# micromouse.net
KiCad netlist of a schematic drawn in EAGLE
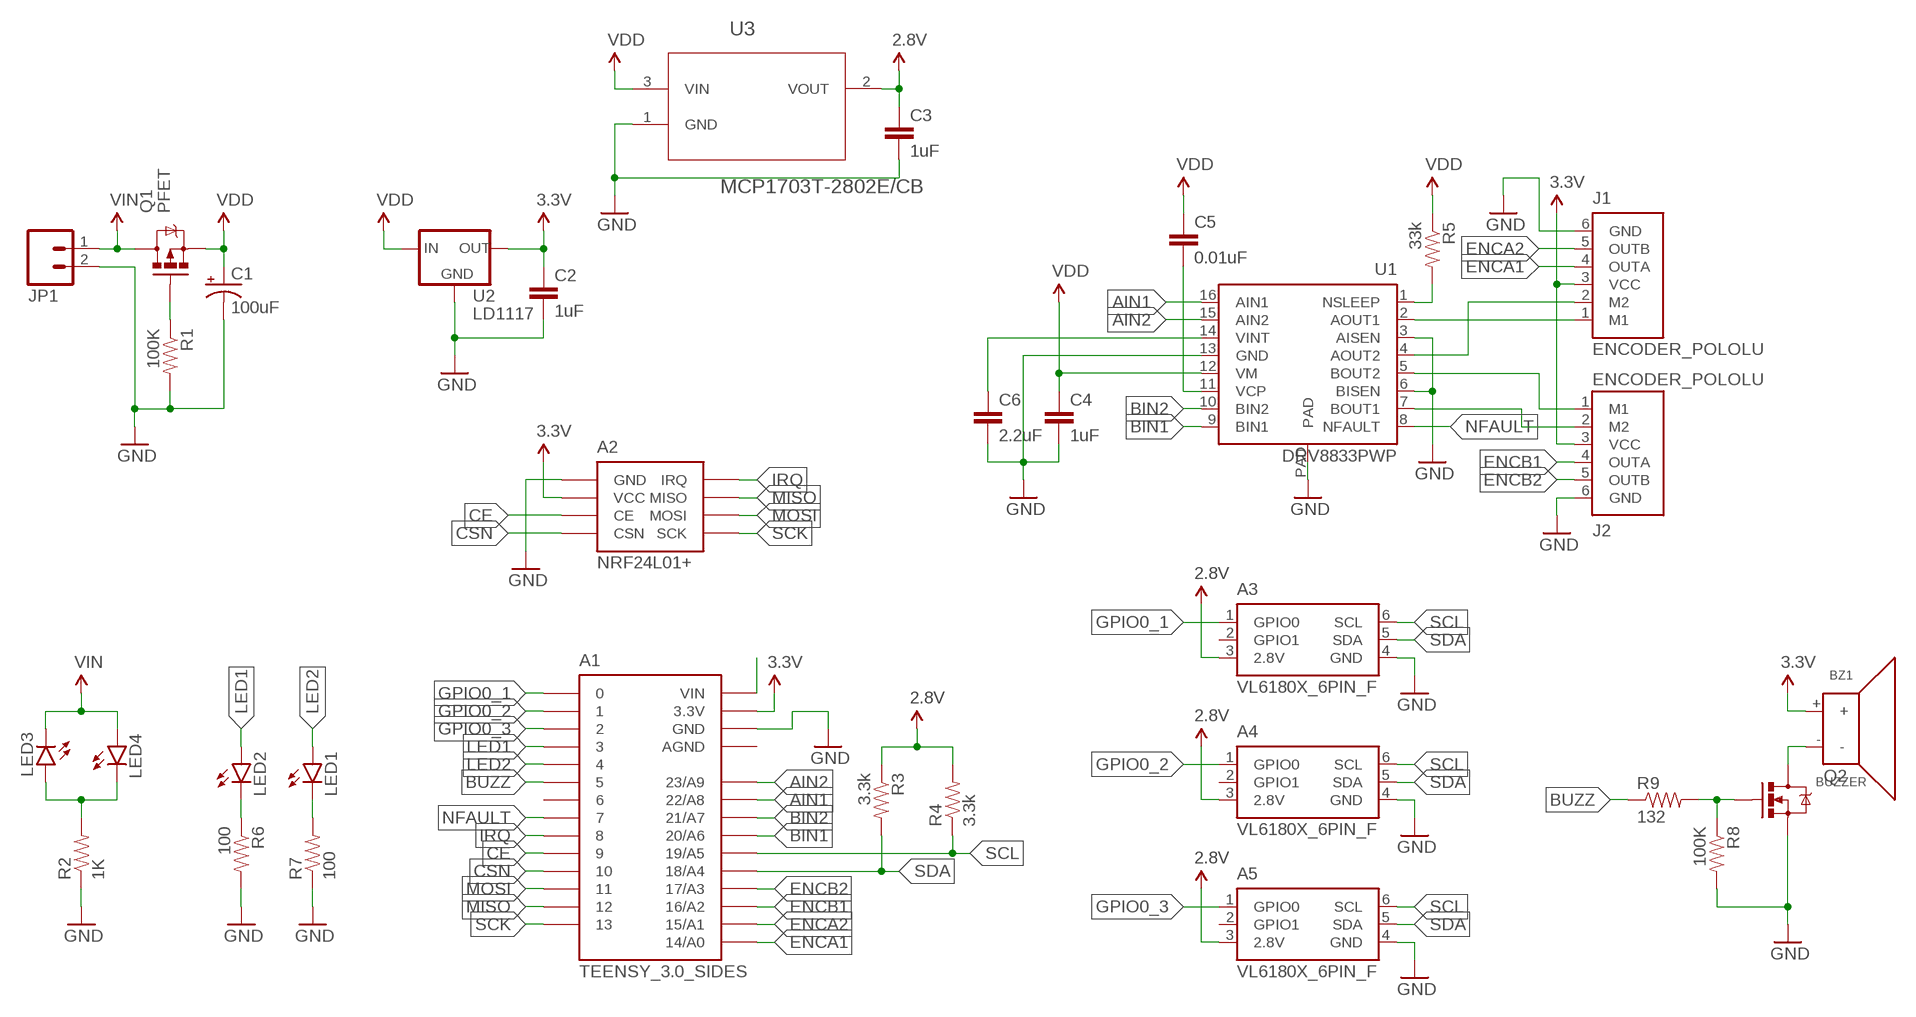
[diagram p0: schematic, sheet 1]

(export (version "E")
  (design (tool "Eeschema 10.0.6"))
  (components
    (comp (ref "A1")
      (value "TEENSY_3.0_SIDES")
      (footprint "eagle-import:TEENSY_3.0_SIDES")
      (libsource (lib "eagle-import") (part "TEENSY_3.0_SIDES"))
    )
    (comp (ref "A2")
      (value "NRF24L01+")
      (footprint "eagle-import:NRF24L01+")
      (libsource (lib "eagle-import") (part "NRF24L01+"))
    )
    (comp (ref "A3")
      (value "VL6180X_6PIN_F")
      (footprint "eagle-import:2X3HEADER")
      (libsource (lib "eagle-import") (part "VL6180X_6PIN_F"))
    )
    (comp (ref "A4")
      (value "VL6180X_6PIN_F")
      (footprint "eagle-import:2X3HEADER")
      (libsource (lib "eagle-import") (part "VL6180X_6PIN_F"))
    )
    (comp (ref "A5")
      (value "VL6180X_6PIN_F")
      (footprint "eagle-import:2X3HEADER")
      (libsource (lib "eagle-import") (part "VL6180X_6PIN_F"))
    )
    (comp (ref "BZ1")
      (value "BUZZER")
      (footprint "eagle-import:BUZZER")
      (libsource (lib "eagle-import") (part "BUZZER"))
    )
    (comp (ref "C1")
      (value "100uF")
      (footprint "eagle-import:CPOL-RADIAL-100UF-25V")
      (libsource (lib "eagle-import") (part "CAP_POLPTH1"))
    )
    (comp (ref "C2")
      (value "1uF")
      (footprint "eagle-import:0603-CAP")
      (libsource (lib "eagle-import") (part "CAP0603-CAP"))
    )
    (comp (ref "C3")
      (value "1uF")
      (footprint "eagle-import:0603-CAP")
      (libsource (lib "eagle-import") (part "CAP0603-CAP"))
    )
    (comp (ref "C4")
      (value "1uF")
      (footprint "eagle-import:0603-CAP")
      (libsource (lib "eagle-import") (part "CAP0603-CAP"))
    )
    (comp (ref "C5")
      (value "0.01uF")
      (footprint "eagle-import:0603-CAP")
      (libsource (lib "eagle-import") (part "CAP0603-CAP"))
    )
    (comp (ref "C6")
      (value "2.2uF")
      (footprint "eagle-import:0603-CAP")
      (libsource (lib "eagle-import") (part "CAP0603-CAP"))
    )
    (comp (ref "J1")
      (value "ENCODER_POLOLU")
      (footprint "eagle-import:1XM06-LOCK")
      (libsource (lib "eagle-import") (part "ENCODER_POLOLU"))
    )
    (comp (ref "J2")
      (value "ENCODER_POLOLU")
      (footprint "eagle-import:1XM06-LOCK")
      (libsource (lib "eagle-import") (part "ENCODER_POLOLU"))
    )
    (comp (ref "JP1")
      (value "M02LOCK_LONGPADS")
      (footprint "eagle-import:1X02_LOCK_LONGPADS")
      (libsource (lib "eagle-import") (part "M02LOCK_LONGPADS"))
    )
    (comp (ref "LED1")
      (value "LED0603")
      (footprint "eagle-import:LED-0603")
      (libsource (lib "eagle-import") (part "LED0603"))
    )
    (comp (ref "LED2")
      (value "LED0603")
      (footprint "eagle-import:LED-0603")
      (libsource (lib "eagle-import") (part "LED0603"))
    )
    (comp (ref "LED3")
      (value "LED0603")
      (footprint "eagle-import:LED-0603")
      (libsource (lib "eagle-import") (part "LED0603"))
    )
    (comp (ref "LED4")
      (value "LED0603")
      (footprint "eagle-import:LED-0603")
      (libsource (lib "eagle-import") (part "LED0603"))
    )
    (comp (ref "Q1")
      (value "PFET")
      (footprint "eagle-import:SOT23-3")
      (libsource (lib "eagle-import") (part "MOSFET-PCHANNEL"))
    )
    (comp (ref "Q2")
      (value "MOSFET-NCHANNELBSS123LT1G")
      (footprint "eagle-import:SOT23-3")
      (libsource (lib "eagle-import") (part "MOSFET-NCHANNELBSS123LT1G"))
    )
    (comp (ref "R1")
      (value "100K")
      (footprint "eagle-import:0603-RES")
      (libsource (lib "eagle-import") (part "RESISTOR0603"))
    )
    (comp (ref "R2")
      (value "1K")
      (footprint "eagle-import:0603-RES")
      (libsource (lib "eagle-import") (part "RESISTOR0603"))
    )
    (comp (ref "R3")
      (value "3.3k")
      (footprint "eagle-import:0603-RES")
      (libsource (lib "eagle-import") (part "RESISTOR0603"))
    )
    (comp (ref "R4")
      (value "3.3k")
      (footprint "eagle-import:0603-RES")
      (libsource (lib "eagle-import") (part "RESISTOR0603"))
    )
    (comp (ref "R5")
      (value "33k")
      (footprint "eagle-import:0603-RES")
      (libsource (lib "eagle-import") (part "RESISTOR0603"))
    )
    (comp (ref "R6")
      (value "100")
      (footprint "eagle-import:0603-RES")
      (libsource (lib "eagle-import") (part "RESISTOR0603"))
    )
    (comp (ref "R7")
      (value "100")
      (footprint "eagle-import:0603-RES")
      (libsource (lib "eagle-import") (part "RESISTOR0603"))
    )
    (comp (ref "R8")
      (value "100K")
      (footprint "eagle-import:0603-RES")
      (libsource (lib "eagle-import") (part "RESISTOR0603"))
    )
    (comp (ref "R9")
      (value "132")
      (footprint "eagle-import:0603-RES")
      (libsource (lib "eagle-import") (part "RESISTOR0603"))
    )
    (comp (ref "U1")
      (value "DRV8833PWP")
      (footprint "eagle-import:HTSSOP-16")
      (libsource (lib "eagle-import") (part "DRV8833PWP"))
    )
    (comp (ref "U2")
      (value "LD1117")
      (footprint "eagle-import:SOT-223")
      (libsource (lib "eagle-import") (part "LD1117"))
    )
    (comp (ref "U3")
      (value "MCP1703T-2802E/CB")
      (footprint "eagle-import:SOT95P300X145-3N")
      (fields (field (name "MPN") "MCP1703T-3002E/CB"))
      (libsource (lib "eagle-import") (part "MCP1703T-3002E/CB"))
    )
  )
  (nets
    (net (code "1") (name "/AGND") (class "Default")
      (node (ref "A1") (pin "AGND") (pinfunction "AGND_AGND") (pintype "power_in"))
    )
    (net (code "2") (name "2.8V") (class "Default")
      (node (ref "A3") (pin "3") (pinfunction "2.8V_3") (pintype "bidirectional"))
      (node (ref "A4") (pin "3") (pinfunction "2.8V_3") (pintype "bidirectional"))
      (node (ref "A5") (pin "3") (pinfunction "2.8V_3") (pintype "bidirectional"))
      (node (ref "C3") (pin "1") (pinfunction "1_1") (pintype "passive"))
      (node (ref "R3") (pin "1") (pinfunction "1_1") (pintype "passive"))
      (node (ref "R4") (pin "2") (pinfunction "2_2") (pintype "passive"))
      (node (ref "U3") (pin "2") (pinfunction "VOUT_2") (pintype "output"))
    )
    (net (code "3") (name "3.3V") (class "Default")
      (node (ref "A1") (pin "3.3V") (pinfunction "3.3V_3.3V") (pintype "power_in"))
      (node (ref "A2") (pin "2") (pinfunction "VCC_2") (pintype "bidirectional"))
      (node (ref "BZ1") (pin "+") (pinfunction "+_+") (pintype "bidirectional"))
      (node (ref "C2") (pin "1") (pinfunction "1_1") (pintype "passive"))
      (node (ref "J1") (pin "3") (pinfunction "VCC_3") (pintype "bidirectional"))
      (node (ref "J2") (pin "3") (pinfunction "VCC_3") (pintype "bidirectional"))
      (node (ref "U2") (pin "2") (pinfunction "OUT_2") (pintype "passive"))
      (node (ref "U2") (pin "4") (pinfunction "OUT_4") (pintype "passive"))
    )
    (net (code "4") (name "AIN1") (class "Default")
      (node (ref "A1") (pin "22/A8") (pinfunction "22/A8_22/A8") (pintype "bidirectional"))
      (node (ref "U1") (pin "16") (pinfunction "AIN1_16") (pintype "bidirectional"))
    )
    (net (code "5") (name "AIN2") (class "Default")
      (node (ref "A1") (pin "23/A9") (pinfunction "23/A9_23/A9") (pintype "bidirectional"))
      (node (ref "U1") (pin "15") (pinfunction "AIN2_15") (pintype "bidirectional"))
    )
    (net (code "6") (name "BIN1") (class "Default")
      (node (ref "A1") (pin "20/A6") (pinfunction "20/A6_20/A6") (pintype "bidirectional"))
      (node (ref "U1") (pin "9") (pinfunction "BIN1_9") (pintype "bidirectional"))
    )
    (net (code "7") (name "BIN2") (class "Default")
      (node (ref "A1") (pin "21/A7") (pinfunction "21/A7_21/A7") (pintype "bidirectional"))
      (node (ref "U1") (pin "10") (pinfunction "BIN2_10") (pintype "bidirectional"))
    )
    (net (code "8") (name "BUZZ") (class "Default")
      (node (ref "A1") (pin "5") (pinfunction "5_5") (pintype "bidirectional"))
      (node (ref "R9") (pin "1") (pinfunction "1_1") (pintype "passive"))
    )
    (net (code "9") (name "CE") (class "Default")
      (node (ref "A1") (pin "9") (pinfunction "9_9") (pintype "bidirectional"))
      (node (ref "A2") (pin "3") (pinfunction "CE_3") (pintype "bidirectional"))
    )
    (net (code "10") (name "CSN") (class "Default")
      (node (ref "A1") (pin "10") (pinfunction "10_10") (pintype "bidirectional"))
      (node (ref "A2") (pin "4") (pinfunction "CSN_4") (pintype "bidirectional"))
    )
    (net (code "11") (name "ENCA1") (class "Default")
      (node (ref "A1") (pin "14/A0") (pinfunction "14/A0_14/A0") (pintype "bidirectional"))
      (node (ref "J1") (pin "4") (pinfunction "OUTA_4") (pintype "bidirectional"))
    )
    (net (code "12") (name "ENCA2") (class "Default")
      (node (ref "A1") (pin "15/A1") (pinfunction "15/A1_15/A1") (pintype "bidirectional"))
      (node (ref "J1") (pin "5") (pinfunction "OUTB_5") (pintype "bidirectional"))
    )
    (net (code "13") (name "ENCB1") (class "Default")
      (node (ref "A1") (pin "16/A2") (pinfunction "16/A2_16/A2") (pintype "bidirectional"))
      (node (ref "J2") (pin "4") (pinfunction "OUTA_4") (pintype "bidirectional"))
    )
    (net (code "14") (name "ENCB2") (class "Default")
      (node (ref "A1") (pin "17/A3") (pinfunction "17/A3_17/A3") (pintype "bidirectional"))
      (node (ref "J2") (pin "5") (pinfunction "OUTB_5") (pintype "bidirectional"))
    )
    (net (code "15") (name "GND") (class "Default")
      (node (ref "A1") (pin "GND") (pinfunction "GND_GND") (pintype "power_in"))
      (node (ref "A2") (pin "1") (pinfunction "GND_1") (pintype "bidirectional"))
      (node (ref "A3") (pin "4") (pinfunction "GND_4") (pintype "bidirectional"))
      (node (ref "A4") (pin "4") (pinfunction "GND_4") (pintype "bidirectional"))
      (node (ref "A5") (pin "4") (pinfunction "GND_4") (pintype "bidirectional"))
      (node (ref "C1") (pin "2") (pinfunction "-_2") (pintype "passive"))
      (node (ref "C2") (pin "2") (pinfunction "2_2") (pintype "passive"))
      (node (ref "C3") (pin "2") (pinfunction "2_2") (pintype "passive"))
      (node (ref "C4") (pin "2") (pinfunction "2_2") (pintype "passive"))
      (node (ref "C6") (pin "2") (pinfunction "2_2") (pintype "passive"))
      (node (ref "J1") (pin "6") (pinfunction "GND_6") (pintype "bidirectional"))
      (node (ref "J2") (pin "6") (pinfunction "GND_6") (pintype "bidirectional"))
      (node (ref "JP1") (pin "2") (pinfunction "2_2") (pintype "passive"))
      (node (ref "Q2") (pin "2") (pinfunction "S_2") (pintype "passive"))
      (node (ref "R1") (pin "2") (pinfunction "2_2") (pintype "passive"))
      (node (ref "R2") (pin "1") (pinfunction "1_1") (pintype "passive"))
      (node (ref "R6") (pin "2") (pinfunction "2_2") (pintype "passive"))
      (node (ref "R7") (pin "1") (pinfunction "1_1") (pintype "passive"))
      (node (ref "R8") (pin "2") (pinfunction "2_2") (pintype "passive"))
      (node (ref "U1") (pin "13") (pinfunction "GND_13") (pintype "bidirectional"))
      (node (ref "U1") (pin "3") (pinfunction "AISEN_3") (pintype "bidirectional"))
      (node (ref "U1") (pin "6") (pinfunction "BISEN_6") (pintype "bidirectional"))
      (node (ref "U1") (pin "PAD") (pinfunction "PAD_PAD") (pintype "bidirectional"))
      (node (ref "U2") (pin "1") (pinfunction "GND_1") (pintype "input"))
      (node (ref "U3") (pin "1") (pinfunction "GND_1") (pintype "passive"))
    )
    (net (code "16") (name "GPIO0_1") (class "Default")
      (node (ref "A1") (pin "0") (pinfunction "0_0") (pintype "bidirectional"))
      (node (ref "A3") (pin "1") (pinfunction "GPIO0_1") (pintype "bidirectional"))
    )
    (net (code "17") (name "GPIO0_2") (class "Default")
      (node (ref "A1") (pin "1") (pinfunction "1_1") (pintype "bidirectional"))
      (node (ref "A4") (pin "1") (pinfunction "GPIO0_1") (pintype "bidirectional"))
    )
    (net (code "18") (name "GPIO0_3") (class "Default")
      (node (ref "A1") (pin "2") (pinfunction "2_2") (pintype "bidirectional"))
      (node (ref "A5") (pin "1") (pinfunction "GPIO0_1") (pintype "bidirectional"))
    )
    (net (code "19") (name "IRQ") (class "Default")
      (node (ref "A1") (pin "8") (pinfunction "8_8") (pintype "bidirectional"))
      (node (ref "A2") (pin "8") (pinfunction "IRQ_8") (pintype "bidirectional"))
    )
    (net (code "20") (name "LED1") (class "Default")
      (node (ref "A1") (pin "3") (pinfunction "3_3") (pintype "bidirectional"))
      (node (ref "LED2") (pin "A") (pinfunction "A_A") (pintype "passive"))
    )
    (net (code "21") (name "LED2") (class "Default")
      (node (ref "A1") (pin "4") (pinfunction "4_4") (pintype "bidirectional"))
      (node (ref "LED1") (pin "A") (pinfunction "A_A") (pintype "passive"))
    )
    (net (code "22") (name "MISO") (class "Default")
      (node (ref "A1") (pin "12") (pinfunction "12_12") (pintype "bidirectional"))
      (node (ref "A2") (pin "7") (pinfunction "MISO_7") (pintype "bidirectional"))
    )
    (net (code "23") (name "MOSI") (class "Default")
      (node (ref "A1") (pin "11") (pinfunction "11_11") (pintype "bidirectional"))
      (node (ref "A2") (pin "6") (pinfunction "MOSI_6") (pintype "bidirectional"))
    )
    (net (code "24") (name "NFAULT") (class "Default")
      (node (ref "A1") (pin "7") (pinfunction "7_7") (pintype "bidirectional"))
      (node (ref "U1") (pin "8") (pinfunction "NFAULT_8") (pintype "bidirectional"))
    )
    (net (code "25") (name "Net-(J1-M1)") (class "Default")
      (node (ref "J1") (pin "1") (pinfunction "M1_1") (pintype "bidirectional"))
      (node (ref "U1") (pin "2") (pinfunction "AOUT1_2") (pintype "bidirectional"))
    )
    (net (code "26") (name "Net-(J1-M2)") (class "Default")
      (node (ref "J1") (pin "2") (pinfunction "M2_2") (pintype "bidirectional"))
      (node (ref "U1") (pin "4") (pinfunction "AOUT2_4") (pintype "bidirectional"))
    )
    (net (code "27") (name "Net-(J2-M1)") (class "Default")
      (node (ref "J2") (pin "1") (pinfunction "M1_1") (pintype "bidirectional"))
      (node (ref "U1") (pin "5") (pinfunction "BOUT2_5") (pintype "bidirectional"))
    )
    (net (code "28") (name "Net-(J2-M2)") (class "Default")
      (node (ref "J2") (pin "2") (pinfunction "M2_2") (pintype "bidirectional"))
      (node (ref "U1") (pin "7") (pinfunction "BOUT1_7") (pintype "bidirectional"))
    )
    (net (code "29") (name "Net-(LED1-PadC)") (class "Default")
      (node (ref "LED1") (pin "C") (pinfunction "C_C") (pintype "passive"))
      (node (ref "R7") (pin "2") (pinfunction "2_2") (pintype "passive"))
    )
    (net (code "30") (name "Net-(LED2-PadC)") (class "Default")
      (node (ref "LED2") (pin "C") (pinfunction "C_C") (pintype "passive"))
      (node (ref "R6") (pin "1") (pinfunction "1_1") (pintype "passive"))
    )
    (net (code "31") (name "Net-(LED3-PadA)") (class "Default")
      (node (ref "LED3") (pin "A") (pinfunction "A_A") (pintype "passive"))
      (node (ref "LED4") (pin "C") (pinfunction "C_C") (pintype "passive"))
      (node (ref "R2") (pin "2") (pinfunction "2_2") (pintype "passive"))
    )
    (net (code "32") (name "Net-(Q1-G)") (class "Default")
      (node (ref "Q1") (pin "1") (pinfunction "G_1") (pintype "passive"))
      (node (ref "R1") (pin "1") (pinfunction "1_1") (pintype "passive"))
    )
    (net (code "33") (name "Net-(Q2-D)") (class "Default")
      (node (ref "BZ1") (pin "-") (pinfunction "-_-") (pintype "bidirectional"))
      (node (ref "Q2") (pin "3") (pinfunction "D_3") (pintype "passive"))
    )
    (net (code "34") (name "Net-(Q2-G)") (class "Default")
      (node (ref "Q2") (pin "1") (pinfunction "G_1") (pintype "passive"))
      (node (ref "R8") (pin "1") (pinfunction "1_1") (pintype "passive"))
      (node (ref "R9") (pin "2") (pinfunction "2_2") (pintype "passive"))
    )
    (net (code "35") (name "Net-(U1-NSLEEP)") (class "Default")
      (node (ref "R5") (pin "2") (pinfunction "2_2") (pintype "passive"))
      (node (ref "U1") (pin "1") (pinfunction "NSLEEP_1") (pintype "bidirectional"))
    )
    (net (code "36") (name "Net-(U1-VCP)") (class "Default")
      (node (ref "C5") (pin "2") (pinfunction "2_2") (pintype "passive"))
      (node (ref "U1") (pin "11") (pinfunction "VCP_11") (pintype "bidirectional"))
    )
    (net (code "37") (name "Net-(U1-VINT)") (class "Default")
      (node (ref "C6") (pin "1") (pinfunction "1_1") (pintype "passive"))
      (node (ref "U1") (pin "14") (pinfunction "VINT_14") (pintype "bidirectional"))
    )
    (net (code "38") (name "SCK") (class "Default")
      (node (ref "A1") (pin "13") (pinfunction "13_13") (pintype "bidirectional"))
      (node (ref "A2") (pin "5") (pinfunction "SCK_5") (pintype "bidirectional"))
    )
    (net (code "39") (name "SCL") (class "Default")
      (node (ref "A1") (pin "19/A5") (pinfunction "19/A5_19/A5") (pintype "bidirectional"))
      (node (ref "A3") (pin "6") (pinfunction "SCL_6") (pintype "bidirectional"))
      (node (ref "A4") (pin "6") (pinfunction "SCL_6") (pintype "bidirectional"))
      (node (ref "A5") (pin "6") (pinfunction "SCL_6") (pintype "bidirectional"))
      (node (ref "R4") (pin "1") (pinfunction "1_1") (pintype "passive"))
    )
    (net (code "40") (name "SDA") (class "Default")
      (node (ref "A1") (pin "18/A4") (pinfunction "18/A4_18/A4") (pintype "bidirectional"))
      (node (ref "A3") (pin "5") (pinfunction "SDA_5") (pintype "bidirectional"))
      (node (ref "A4") (pin "5") (pinfunction "SDA_5") (pintype "bidirectional"))
      (node (ref "A5") (pin "5") (pinfunction "SDA_5") (pintype "bidirectional"))
      (node (ref "R3") (pin "2") (pinfunction "2_2") (pintype "passive"))
    )
    (net (code "41") (name "VDD") (class "Default")
      (node (ref "C1") (pin "1") (pinfunction "+_1") (pintype "passive"))
      (node (ref "C4") (pin "1") (pinfunction "1_1") (pintype "passive"))
      (node (ref "C5") (pin "1") (pinfunction "1_1") (pintype "passive"))
      (node (ref "Q1") (pin "2") (pinfunction "S_2") (pintype "passive"))
      (node (ref "R5") (pin "1") (pinfunction "1_1") (pintype "passive"))
      (node (ref "U1") (pin "12") (pinfunction "VM_12") (pintype "bidirectional"))
      (node (ref "U2") (pin "3") (pinfunction "IN_3") (pintype "input"))
      (node (ref "U3") (pin "3") (pinfunction "VIN_3") (pintype "input"))
    )
    (net (code "42") (name "VIN") (class "Default")
      (node (ref "JP1") (pin "1") (pinfunction "1_1") (pintype "passive"))
      (node (ref "LED3") (pin "C") (pinfunction "C_C") (pintype "passive"))
      (node (ref "LED4") (pin "A") (pinfunction "A_A") (pintype "passive"))
      (node (ref "Q1") (pin "3") (pinfunction "D_3") (pintype "passive"))
    )
    (net (code "43") (name "unconnected-(A1-Pad6)") (class "Default")
      (node (ref "A1") (pin "6") (pinfunction "6_6") (pintype "bidirectional"))
    )
    (net (code "44") (name "unconnected-(A1-PadVIN)") (class "Default")
      (node (ref "A1") (pin "VIN") (pinfunction "VIN_VIN") (pintype "power_in"))
    )
    (net (code "45") (name "unconnected-(A3-GPIO1-Pad2)") (class "Default")
      (node (ref "A3") (pin "2") (pinfunction "GPIO1_2") (pintype "bidirectional"))
    )
    (net (code "46") (name "unconnected-(A4-GPIO1-Pad2)") (class "Default")
      (node (ref "A4") (pin "2") (pinfunction "GPIO1_2") (pintype "bidirectional"))
    )
    (net (code "47") (name "unconnected-(A5-GPIO1-Pad2)") (class "Default")
      (node (ref "A5") (pin "2") (pinfunction "GPIO1_2") (pintype "bidirectional"))
    )
  )
)
